# Sheet1.net
KiCad netlist of a schematic drawn in Altium Designer
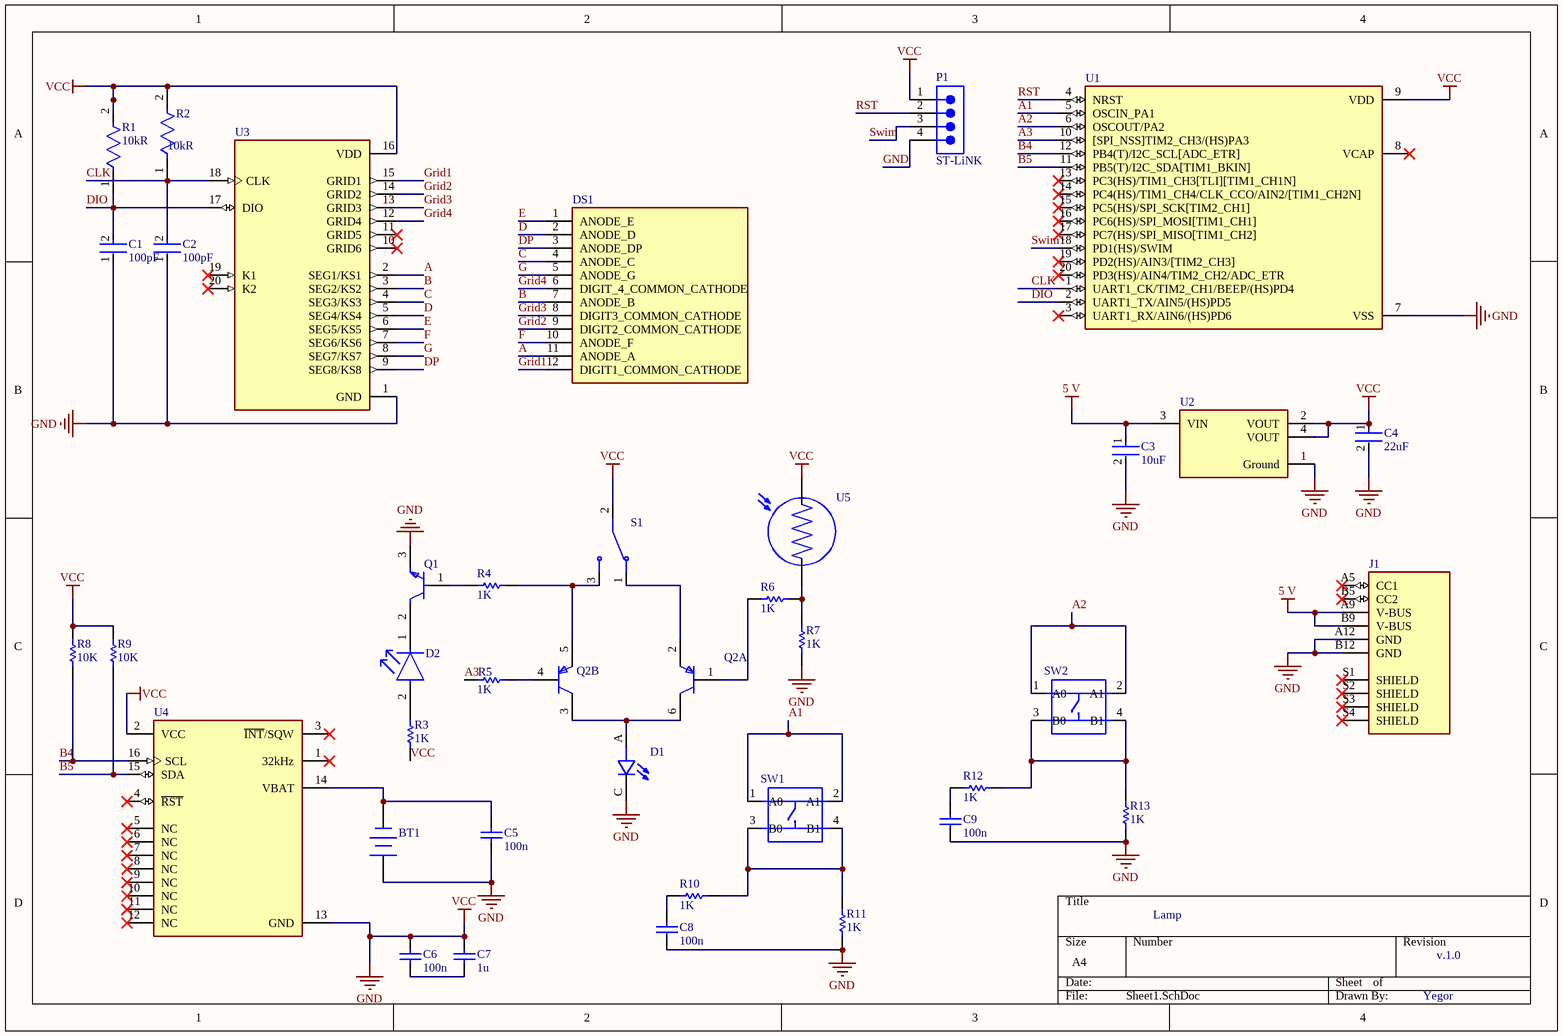
[diagram p0: Sheet1.SchDoc]

(export (version "E")
  (design (tool "Eeschema 10.0.6"))
  (components
    (comp (ref "BT1")
      (value "~")
      (footprint "PANA-CR-2032HFN")
      (description "Coin Cell Battery, 225 mAh, 0.2 mA, 3 V, -30 to 60 degC, Bulk")
      (fields (field (name "MANUFACTURER") "Panasonic"))
      (libsource (lib "Components - 25.08.25 - 13.52") (part "CMP-2000-05296-1"))
    )
    (comp (ref "C1")
      (value "100pF")
      (footprint "FP-C1608-080-0_1-MFG")
      (description "Multilayer Ceramic Capacitors 100pF ±5% 50V C0G SMD 0603")
      (fields (field (name "VOLTAGE") "50V") (field (name "TOLERANCE") "5%"))
      (libsource (lib "Components - 25.08.25 - 11.32") (part "CMP-08246-002637-1"))
    )
    (comp (ref "C2")
      (value "100pF")
      (footprint "FP-C1608-080-0_1-MFG")
      (description "Multilayer Ceramic Capacitors 100pF ±5% 50V C0G SMD 0603")
      (fields (field (name "VOLTAGE") "50V") (field (name "TOLERANCE") "5%"))
      (libsource (lib "Components - 25.08.25 - 11.32") (part "CMP-08246-002637-1"))
    )
    (comp (ref "C3")
      (value "10uF")
      (footprint "FP-CL21-IPC_A")
      (description "CL21 Series 0805 10uF 10V ±20% Tolerance X5R Multilayer Ceramic Chip Capacitor")
      (fields (field (name "TOLERANCE") "20%"))
      (libsource (lib "Components - 25.08.25 - 12.18") (part "CMP-13271-002245-1"))
    )
    (comp (ref "C4")
      (value "22uF")
      (footprint "FP-CL32-IPC_A")
      (description "Cap Ceramic 22uF 6.3V X7R ±20% SMD 1210 +125°C Embossed T/R")
      (fields (field (name "TOLERANCE") "20%"))
      (libsource (lib "Components - 25.08.25 - 12.17") (part "CMP-13271-001877-1"))
    )
    (comp (ref "C5")
      (value "100n")
      (description "Capacitor")
      (libsource (lib "Simulation Generic Components") (part "Capacitor"))
    )
    (comp (ref "C6")
      (value "100n")
      (description "Capacitor")
      (libsource (lib "Simulation Generic Components") (part "Capacitor"))
    )
    (comp (ref "C7")
      (value "1u")
      (description "Capacitor")
      (libsource (lib "Simulation Generic Components") (part "Capacitor"))
    )
    (comp (ref "C8")
      (value "100n")
      (description "Capacitor")
      (libsource (lib "Simulation Generic Components") (part "Capacitor"))
    )
    (comp (ref "C9")
      (value "100n")
      (description "Capacitor")
      (libsource (lib "Simulation Generic Components") (part "Capacitor"))
    )
    (comp (ref "D1")
      (value "~")
      (footprint "LEDC1608X65N")
      (description "CHIP LED WHITE 0603 TOP VIEW")
      (fields (field (name "MP") "LTW-C191TLA"))
      (libsource (lib "LTW-C191TLA") (part "LTW-C191TLA"))
    )
    (comp (ref "D2")
      (value "~")
      (footprint "FP-6_541-5092_01-4-MFG")
      (description "LED RED 0603 SMD")
      (fields
        (field (name "MANUFACTURER") "Vishay")
        (field (name "MANUFACTURER PART NUMBER") "VLMS1300-GS08")
      )
      (libsource (lib "Components - 25.08.25 - 21.29") (part "CMP-02520-000012-1"))
    )
    (comp (ref "DS1")
      (value "~")
      (footprint "AVAGO_HDSP-B09G")
      (fields (field (name "MF") "Broadcom / Avago") (field (name "MP") "HDSP-B09G"))
      (libsource (lib "HDSP-B09G") (part "HDSP-B09G"))
    )
    (comp (ref "J1")
      (value "~")
      (footprint "CUI_UJC-HP-3-SMT-TR")
      (fields (field (name "MP") "UJC-HP-3-SMT-TR"))
      (libsource (lib "UJC-HP-3-SMT-TR") (part "UJC-HP-3-SMT-TR"))
    )
    (comp (ref "P1")
      (value "ST-LiNK")
      (footprint "61300411021")
      (libsource (lib "Components - 25.08.25 - 11.48") (part "CMP-1502-01063-3"))
    )
    (comp (ref "Q1")
      (value "~")
      (footprint "PLZZ0004CA-A_MFG")
      (description "Trans GP BJT NPN 50V 1A 4-Pin(3+Tab) UPAK T/R")
      (libsource (lib "Components - 25.08.25 - 21.28") (part "CMP-00572-18697870-1"))
    )
    (comp (ref "Q2")
      (value "~")
      (footprint "SOT95P280X145-6_P6_064_N")
      (description "Transistor, Bjt, Pair, Pnp, 11V V(Br)Ceo, 14Ma I(C), So")
      (libsource (lib "Components - 25.08.25 - 12.53") (part "CMP-00572-88253858-3"))
    )
    (comp (ref "R1")
      (value "10kR")
      (footprint "FP-CRCW1206-e3-IPC_B")
      (description "RES Thick Film, 10kΩ, 1%, 0.25W, 100ppm/°C, 1206")
      (fields (field (name "TOLERANCE") "1%"))
      (libsource (lib "Components - 25.08.25 - 11.27") (part "CMP-2003-04807-2"))
    )
    (comp (ref "R2")
      (value "10kR")
      (footprint "FP-CRCW1206-e3-IPC_B")
      (description "RES Thick Film, 10kΩ, 1%, 0.25W, 100ppm/°C, 1206")
      (fields (field (name "TOLERANCE") "1%"))
      (libsource (lib "Components - 25.08.25 - 11.27") (part "CMP-2003-04807-2"))
    )
    (comp (ref "R3")
      (value "1K")
      (description "Resistor")
      (libsource (lib "Simulation Generic Components") (part "Resistor"))
    )
    (comp (ref "R4")
      (value "1K")
      (description "Resistor")
      (libsource (lib "Simulation Generic Components") (part "Resistor"))
    )
    (comp (ref "R5")
      (value "1K")
      (description "Resistor")
      (libsource (lib "Simulation Generic Components") (part "Resistor"))
    )
    (comp (ref "R6")
      (value "1K")
      (description "Resistor")
      (libsource (lib "Simulation Generic Components") (part "Resistor"))
    )
    (comp (ref "R7")
      (value "1K")
      (description "Resistor")
      (libsource (lib "Simulation Generic Components") (part "Resistor"))
    )
    (comp (ref "R8")
      (value "10K")
      (description "Resistor")
      (libsource (lib "Simulation Generic Components") (part "Resistor"))
    )
    (comp (ref "R9")
      (value "10K")
      (description "Resistor")
      (libsource (lib "Simulation Generic Components") (part "Resistor"))
    )
    (comp (ref "R10")
      (value "1K")
      (description "Resistor")
      (libsource (lib "Simulation Generic Components") (part "Resistor"))
    )
    (comp (ref "R11")
      (value "1K")
      (description "Resistor")
      (libsource (lib "Simulation Generic Components") (part "Resistor"))
    )
    (comp (ref "R12")
      (value "1K")
      (description "Resistor")
      (libsource (lib "Simulation Generic Components") (part "Resistor"))
    )
    (comp (ref "R13")
      (value "1K")
      (description "Resistor")
      (libsource (lib "Simulation Generic Components") (part "Resistor"))
    )
    (comp (ref "S1")
      (value "~")
      (footprint "SW_MINI-SPDT-SW")
      (fields (field (name "MP") "MINI-SPDT-SW"))
      (libsource (lib "MINI-SPDT-SW") (part "MINI-SPDT-SW"))
    )
    (comp (ref "SW1")
      (value "~")
      (footprint "SW4-SMD-5.2X5.2X1.5MM")
      (description "Switch Tactile N.O. SPST Button Gull Wing 0.05A 12VDC 3.43N SMD T/R")
      (fields (field (name "MF") "ALPS") (field (name "MP") "SKQGAKE010"))
      (libsource (lib "SMD-BUTTON_4P-5.2X5.2X1.5MM-SKQGAKE010_") (part "SMD-BUTTON(4P-5.2X5.2X1.5MM-SKQGAKE010)"))
    )
    (comp (ref "SW2")
      (value "~")
      (footprint "SW4-SMD-5.2X5.2X1.5MM")
      (description "Switch Tactile N.O. SPST Button Gull Wing 0.05A 12VDC 3.43N SMD T/R")
      (fields (field (name "MF") "ALPS") (field (name "MP") "SKQGAKE010"))
      (libsource (lib "SMD-BUTTON_4P-5.2X5.2X1.5MM-SKQGAKE010_") (part "SMD-BUTTON(4P-5.2X5.2X1.5MM-SKQGAKE010)"))
    )
    (comp (ref "U1")
      (value "~")
      (footprint "SOP65P640X120-20N")
      (description "STM8 series Microcontroller IC 8-Bit 16MHz 8KB (8K x 8) FLASH 20-TSSOP")
      (fields (field (name "MF") "STMicroelectronics") (field (name "MP") "STM8S103F3P6"))
      (libsource (lib "STM8S103F3P6") (part "STM8S103F3P6"))
    )
    (comp (ref "U2")
      (value "~")
      (footprint "FP-AMS1117-IPC_A")
      (description "LDO Voltage Regulators 1A, 3.3V")
      (fields
        (field (name "MANUFACTURER PART NUMBER") "AMS1117-3.3")
        (field (name "OCTOPART") "https://octopart.com/ams1117-3.3-advanced+monolithic+systems-25899300")
      )
      (libsource (lib "Components - 25.08.25 - 12.03") (part "CMP-209535-000001-1"))
    )
    (comp (ref "U3")
      (value "~")
      (footprint "DIP778W43P254L2612H431Q20N")
      (description "LED Drive Control Special Circuit")
      (fields (field (name "MF") "Titan Micro Electronics") (field (name "MP") "TM1637"))
      (libsource (lib "TM1637") (part "TM1637"))
    )
    (comp (ref "U4")
      (value "~")
      (footprint "FP-W16-H2-MFG")
      (description "IC RTC CLK/CALENDAR I2C 16-SOIC")
      (libsource (lib "Components - 25.08.25 - 13.49") (part "CMP-0254-00375-2"))
    )
    (comp (ref "U5")
      (value "~")
      (footprint "XDCR_PDV-P8003")
      (description "CdS Cells 520nm 16 ~ 33kOhms @ 10 lux")
      (fields (field (name "MF") "Advanced Photonix") (field (name "MP") "PDV-P8003"))
      (libsource (lib "PDV-P8003") (part "PDV-P8003"))
    )
  )
  (nets
    (net (code "1") (name "/A") (class "Default")
      (node (ref "DS1") (pin "11") (pinfunction "ANODE_A_11") (pintype "passive"))
      (node (ref "U3") (pin "2") (pinfunction "SEG1/KS1_2") (pintype "output"))
    )
    (net (code "2") (name "/A1") (class "Default")
      (node (ref "SW1") (pin "1") (pinfunction "A0_1") (pintype "bidirectional"))
      (node (ref "SW1") (pin "2") (pinfunction "A1_2") (pintype "bidirectional"))
      (node (ref "U1") (pin "5") (pinfunction "OSCIN_PA1_5") (pintype "bidirectional"))
    )
    (net (code "3") (name "/A2") (class "Default")
      (node (ref "SW2") (pin "1") (pinfunction "A0_1") (pintype "bidirectional"))
      (node (ref "SW2") (pin "2") (pinfunction "A1_2") (pintype "bidirectional"))
      (node (ref "U1") (pin "6") (pinfunction "OSCOUT/PA2_6") (pintype "bidirectional"))
    )
    (net (code "4") (name "/A3") (class "Default")
      (node (ref "R5") (pin "2") (pinfunction "2_2") (pintype "passive"))
      (node (ref "U1") (pin "10") (pinfunction "[SPI_NSS]TIM2_CH3/(HS)PA3_10") (pintype "bidirectional"))
    )
    (net (code "5") (name "/B") (class "Default")
      (node (ref "DS1") (pin "7") (pinfunction "ANODE_B_7") (pintype "passive"))
      (node (ref "U3") (pin "3") (pinfunction "SEG2/KS2_3") (pintype "output"))
    )
    (net (code "6") (name "/B4") (class "Default")
      (node (ref "R8") (pin "1") (pinfunction "1_1") (pintype "passive"))
      (node (ref "U1") (pin "12") (pinfunction "PB4(T)/I2C_SCL[ADC_ETR]_12") (pintype "bidirectional"))
      (node (ref "U4") (pin "16") (pinfunction "SCL_16") (pintype "input"))
    )
    (net (code "7") (name "/B5") (class "Default")
      (node (ref "R9") (pin "1") (pinfunction "1_1") (pintype "passive"))
      (node (ref "U1") (pin "11") (pinfunction "PB5(T)/I2C_SDA[TIM1_BKIN]_11") (pintype "bidirectional"))
      (node (ref "U4") (pin "15") (pinfunction "SDA_15") (pintype "bidirectional"))
    )
    (net (code "8") (name "/C") (class "Default")
      (node (ref "DS1") (pin "4") (pinfunction "ANODE_C_4") (pintype "passive"))
      (node (ref "U3") (pin "4") (pinfunction "SEG3/KS3_4") (pintype "output"))
    )
    (net (code "9") (name "/CLK") (class "Default")
      (node (ref "C2") (pin "2") (pinfunction "2_2") (pintype "passive"))
      (node (ref "R2") (pin "1") (pinfunction "1_1") (pintype "passive"))
      (node (ref "U1") (pin "1") (pinfunction "UART1_CK/TIM2_CH1/BEEP/(HS)PD4_1") (pintype "bidirectional"))
      (node (ref "U3") (pin "18") (pinfunction "CLK_18") (pintype "input"))
    )
    (net (code "10") (name "/D") (class "Default")
      (node (ref "DS1") (pin "2") (pinfunction "ANODE_D_2") (pintype "passive"))
      (node (ref "U3") (pin "5") (pinfunction "SEG4/KS4_5") (pintype "output"))
    )
    (net (code "11") (name "/DIO") (class "Default")
      (node (ref "C1") (pin "2") (pinfunction "2_2") (pintype "passive"))
      (node (ref "R1") (pin "1") (pinfunction "1_1") (pintype "passive"))
      (node (ref "U1") (pin "2") (pinfunction "UART1_TX/AIN5/(HS)PD5_2") (pintype "bidirectional"))
      (node (ref "U3") (pin "17") (pinfunction "DIO_17") (pintype "bidirectional"))
    )
    (net (code "12") (name "/DP") (class "Default")
      (node (ref "DS1") (pin "3") (pinfunction "ANODE_DP_3") (pintype "passive"))
      (node (ref "U3") (pin "9") (pinfunction "SEG8/KS8_9") (pintype "output"))
    )
    (net (code "13") (name "/E") (class "Default")
      (node (ref "DS1") (pin "1") (pinfunction "ANODE_E_1") (pintype "passive"))
      (node (ref "U3") (pin "6") (pinfunction "SEG5/KS5_6") (pintype "output"))
    )
    (net (code "14") (name "/F") (class "Default")
      (node (ref "DS1") (pin "10") (pinfunction "ANODE_F_10") (pintype "passive"))
      (node (ref "U3") (pin "7") (pinfunction "SEG6/KS6_7") (pintype "output"))
    )
    (net (code "15") (name "/G") (class "Default")
      (node (ref "DS1") (pin "5") (pinfunction "ANODE_G_5") (pintype "passive"))
      (node (ref "U3") (pin "8") (pinfunction "SEG7/KS7_8") (pintype "output"))
    )
    (net (code "16") (name "/Grid1") (class "Default")
      (node (ref "DS1") (pin "12") (pinfunction "DIGIT1_COMMON_CATHODE_12") (pintype "passive"))
      (node (ref "U3") (pin "15") (pinfunction "GRID1_15") (pintype "output"))
    )
    (net (code "17") (name "/Grid2") (class "Default")
      (node (ref "DS1") (pin "9") (pinfunction "DIGIT2_COMMON_CATHODE_9") (pintype "passive"))
      (node (ref "U3") (pin "14") (pinfunction "GRID2_14") (pintype "output"))
    )
    (net (code "18") (name "/Grid3") (class "Default")
      (node (ref "DS1") (pin "8") (pinfunction "DIGIT3_COMMON_CATHODE_8") (pintype "passive"))
      (node (ref "U3") (pin "13") (pinfunction "GRID3_13") (pintype "output"))
    )
    (net (code "19") (name "/Grid4") (class "Default")
      (node (ref "DS1") (pin "6") (pinfunction "DIGIT_4_COMMON_CATHODE_6") (pintype "passive"))
      (node (ref "U3") (pin "12") (pinfunction "GRID4_12") (pintype "output"))
    )
    (net (code "20") (name "/RST") (class "Default")
      (node (ref "P1") (pin "2") (pinfunction "2_2") (pintype "passive"))
      (node (ref "U1") (pin "4") (pinfunction "NRST_4") (pintype "bidirectional"))
    )
    (net (code "21") (name "/Swim") (class "Default")
      (node (ref "P1") (pin "3") (pinfunction "3_3") (pintype "passive"))
      (node (ref "U1") (pin "18") (pinfunction "PD1(HS)/SWIM_18") (pintype "bidirectional"))
    )
    (net (code "22") (name "5 V") (class "Default")
      (node (ref "C3") (pin "1") (pinfunction "1_1") (pintype "passive"))
      (node (ref "J1") (pin "A9") (pinfunction "V-BUS_A9") (pintype "power_in"))
      (node (ref "J1") (pin "B9") (pinfunction "V-BUS_B9") (pintype "power_in"))
      (node (ref "U2") (pin "3") (pinfunction "VIN_3") (pintype "power_in"))
    )
    (net (code "23") (name "GND") (class "Default")
      (node (ref "BT1") (pin "1") (pinfunction "+_1") (pintype "passive"))
      (node (ref "C1") (pin "1") (pinfunction "1_1") (pintype "passive"))
      (node (ref "C2") (pin "1") (pinfunction "1_1") (pintype "passive"))
      (node (ref "C3") (pin "2") (pinfunction "2_2") (pintype "passive"))
      (node (ref "C4") (pin "1") (pinfunction "1_1") (pintype "passive"))
      (node (ref "C4") (pin "2") (pinfunction "2_2") (pintype "passive"))
      (node (ref "C5") (pin "1") (pinfunction "1_1") (pintype "passive"))
      (node (ref "C6") (pin "2") (pinfunction "2_2") (pintype "passive"))
      (node (ref "C7") (pin "2") (pinfunction "2_2") (pintype "passive"))
      (node (ref "C8") (pin "1") (pinfunction "1_1") (pintype "passive"))
      (node (ref "C9") (pin "1") (pinfunction "1_1") (pintype "passive"))
      (node (ref "D1") (pin "C") (pinfunction "C_C") (pintype "passive"))
      (node (ref "J1") (pin "A12") (pinfunction "GND_A12") (pintype "power_in"))
      (node (ref "J1") (pin "B12") (pinfunction "GND_B12") (pintype "power_in"))
      (node (ref "P1") (pin "1") (pinfunction "1_1") (pintype "passive"))
      (node (ref "P1") (pin "4") (pinfunction "4_4") (pintype "passive"))
      (node (ref "Q1") (pin "3") (pinfunction "EMITTER_3") (pintype "passive"))
      (node (ref "R1") (pin "2") (pinfunction "2_2") (pintype "passive"))
      (node (ref "R11") (pin "1") (pinfunction "1_1") (pintype "passive"))
      (node (ref "R13") (pin "1") (pinfunction "1_1") (pintype "passive"))
      (node (ref "R2") (pin "2") (pinfunction "2_2") (pintype "passive"))
      (node (ref "R3") (pin "1") (pinfunction "1_1") (pintype "passive"))
      (node (ref "R7") (pin "1") (pinfunction "1_1") (pintype "passive"))
      (node (ref "R8") (pin "2") (pinfunction "2_2") (pintype "passive"))
      (node (ref "R9") (pin "2") (pinfunction "2_2") (pintype "passive"))
      (node (ref "S1") (pin "2") (pinfunction "2_2") (pintype "passive"))
      (node (ref "U1") (pin "7") (pinfunction "VSS_7") (pintype "power_in"))
      (node (ref "U1") (pin "9") (pinfunction "VDD_9") (pintype "power_in"))
      (node (ref "U2") (pin "1") (pinfunction "Ground_1") (pintype "power_in"))
      (node (ref "U2") (pin "2") (pinfunction "VOUT_2") (pintype "passive"))
      (node (ref "U2") (pin "4") (pinfunction "VOUT_4") (pintype "passive"))
      (node (ref "U3") (pin "1") (pinfunction "GND_1") (pintype "power_in"))
      (node (ref "U3") (pin "16") (pinfunction "VDD_16") (pintype "power_in"))
      (node (ref "U4") (pin "13") (pinfunction "GND_13") (pintype "power_in"))
      (node (ref "U4") (pin "2") (pinfunction "VCC_2") (pintype "power_in"))
      (node (ref "U5") (pin "2") (pinfunction "2_2") (pintype "passive"))
    )
    (net (code "24") (name "Net-(BT1--)") (class "Default")
      (node (ref "BT1") (pin "2") (pinfunction "-_2") (pintype "passive"))
      (node (ref "C5") (pin "2") (pinfunction "2_2") (pintype "passive"))
      (node (ref "U4") (pin "14") (pinfunction "VBAT_14") (pintype "power_in"))
    )
    (net (code "25") (name "Net-(C6-Pad1)") (class "Default")
      (node (ref "C6") (pin "1") (pinfunction "1_1") (pintype "passive"))
      (node (ref "C7") (pin "1") (pinfunction "1_1") (pintype "passive"))
    )
    (net (code "26") (name "Net-(C8-Pad2)") (class "Default")
      (node (ref "C8") (pin "2") (pinfunction "2_2") (pintype "passive"))
      (node (ref "R10") (pin "1") (pinfunction "1_1") (pintype "passive"))
    )
    (net (code "27") (name "Net-(C9-Pad2)") (class "Default")
      (node (ref "C9") (pin "2") (pinfunction "2_2") (pintype "passive"))
      (node (ref "R12") (pin "1") (pinfunction "1_1") (pintype "passive"))
    )
    (net (code "28") (name "Net-(D2-A)") (class "Default")
      (node (ref "D2") (pin "2") (pinfunction "A_2") (pintype "passive"))
      (node (ref "R3") (pin "2") (pinfunction "2_2") (pintype "passive"))
    )
    (net (code "29") (name "Net-(D2-C)") (class "Default")
      (node (ref "D2") (pin "1") (pinfunction "C_1") (pintype "passive"))
      (node (ref "Q1") (pin "2") (pinfunction "COLLECTOR_2") (pintype "passive"))
    )
    (net (code "30") (name "Net-(Q1-BASE)") (class "Default")
      (node (ref "Q1") (pin "1") (pinfunction "BASE_1") (pintype "passive"))
      (node (ref "R4") (pin "1") (pinfunction "1_1") (pintype "passive"))
    )
    (net (code "31") (name "Net-(Q2A-1_BASE)") (class "Default")
      (node (ref "Q2") (pin "1") (pinfunction "1_BASE_1") (pintype "passive"))
      (node (ref "R6") (pin "1") (pinfunction "1_1") (pintype "passive"))
    )
    (net (code "32") (name "Net-(Q2A-1_COLLECTOR)") (class "Default")
      (node (ref "D1") (pin "A") (pinfunction "A_A") (pintype "passive"))
      (node (ref "Q2") (pin "3") (pinfunction "2_COLLECTOR_3") (pintype "passive"))
      (node (ref "Q2") (pin "6") (pinfunction "1_COLLECTOR_6") (pintype "passive"))
    )
    (net (code "33") (name "Net-(Q2A-1_EMITTER)") (class "Default")
      (node (ref "Q2") (pin "2") (pinfunction "1_EMITTER_2") (pintype "passive"))
      (node (ref "S1") (pin "1") (pinfunction "1_1") (pintype "passive"))
    )
    (net (code "34") (name "Net-(Q2B-2_BASE)") (class "Default")
      (node (ref "Q2") (pin "4") (pinfunction "2_BASE_4") (pintype "passive"))
      (node (ref "R5") (pin "1") (pinfunction "1_1") (pintype "passive"))
    )
    (net (code "35") (name "Net-(Q2B-2_EMITTER)") (class "Default")
      (node (ref "Q2") (pin "5") (pinfunction "2_EMITTER_5") (pintype "passive"))
      (node (ref "R4") (pin "2") (pinfunction "2_2") (pintype "passive"))
      (node (ref "S1") (pin "3") (pinfunction "3_3") (pintype "passive"))
    )
    (net (code "36") (name "Net-(R6-Pad2)") (class "Default")
      (node (ref "R6") (pin "2") (pinfunction "2_2") (pintype "passive"))
      (node (ref "R7") (pin "2") (pinfunction "2_2") (pintype "passive"))
      (node (ref "U5") (pin "1") (pinfunction "1_1") (pintype "passive"))
    )
    (net (code "37") (name "Net-(SW1-B0)") (class "Default")
      (node (ref "R10") (pin "2") (pinfunction "2_2") (pintype "passive"))
      (node (ref "R11") (pin "2") (pinfunction "2_2") (pintype "passive"))
      (node (ref "SW1") (pin "3") (pinfunction "B0_3") (pintype "bidirectional"))
      (node (ref "SW1") (pin "4") (pinfunction "B1_4") (pintype "bidirectional"))
    )
    (net (code "38") (name "Net-(SW2-B0)") (class "Default")
      (node (ref "R12") (pin "2") (pinfunction "2_2") (pintype "passive"))
      (node (ref "R13") (pin "2") (pinfunction "2_2") (pintype "passive"))
      (node (ref "SW2") (pin "3") (pinfunction "B0_3") (pintype "bidirectional"))
      (node (ref "SW2") (pin "4") (pinfunction "B1_4") (pintype "bidirectional"))
    )
    (net (code "39") (name "unconnected-(J1-CC1-PadA5)") (class "Default")
      (node (ref "J1") (pin "A5") (pinfunction "CC1_A5") (pintype "bidirectional+no_connect"))
    )
    (net (code "40") (name "unconnected-(J1-CC2-PadB5)") (class "Default")
      (node (ref "J1") (pin "B5") (pinfunction "CC2_B5") (pintype "bidirectional+no_connect"))
    )
    (net (code "41") (name "unconnected-(J1-SHIELD-PadS1)") (class "Default")
      (node (ref "J1") (pin "S1") (pinfunction "SHIELD_S1") (pintype "passive+no_connect"))
    )
    (net (code "42") (name "unconnected-(J1-SHIELD-PadS2)") (class "Default")
      (node (ref "J1") (pin "S2") (pinfunction "SHIELD_S2") (pintype "passive+no_connect"))
    )
    (net (code "43") (name "unconnected-(J1-SHIELD-PadS3)") (class "Default")
      (node (ref "J1") (pin "S3") (pinfunction "SHIELD_S3") (pintype "passive+no_connect"))
    )
    (net (code "44") (name "unconnected-(J1-SHIELD-PadS4)") (class "Default")
      (node (ref "J1") (pin "S4") (pinfunction "SHIELD_S4") (pintype "passive+no_connect"))
    )
    (net (code "45") (name "unconnected-(U1-PC3(HS){slash}TIM1_CH3[TLI][TIM1_CH1N]-Pad13)") (class "Default")
      (node (ref "U1") (pin "13") (pinfunction "PC3(HS)/TIM1_CH3[TLI][TIM1_CH1N]_13") (pintype "bidirectional+no_connect"))
    )
    (net (code "46") (name "unconnected-(U1-PC4(HS){slash}TIM1_CH4{slash}CLK_CCO{slash}AIN2{slash}[TIM1_CH2N]-Pad14)") (class "Default")
      (node (ref "U1") (pin "14") (pinfunction "PC4(HS)/TIM1_CH4/CLK_CCO/AIN2/[TIM1_CH2N]_14") (pintype "bidirectional+no_connect"))
    )
    (net (code "47") (name "unconnected-(U1-PC5(HS){slash}SPI_SCK[TIM2_CH1]-Pad15)") (class "Default")
      (node (ref "U1") (pin "15") (pinfunction "PC5(HS)/SPI_SCK[TIM2_CH1]_15") (pintype "bidirectional+no_connect"))
    )
    (net (code "48") (name "unconnected-(U1-PC6(HS){slash}SPI_MOSI[TIM1_CH1]-Pad16)") (class "Default")
      (node (ref "U1") (pin "16") (pinfunction "PC6(HS)/SPI_MOSI[TIM1_CH1]_16") (pintype "bidirectional+no_connect"))
    )
    (net (code "49") (name "unconnected-(U1-PC7(HS){slash}SPI_MISO[TIM1_CH2]-Pad17)") (class "Default")
      (node (ref "U1") (pin "17") (pinfunction "PC7(HS)/SPI_MISO[TIM1_CH2]_17") (pintype "bidirectional+no_connect"))
    )
    (net (code "50") (name "unconnected-(U1-PD2(HS){slash}AIN3{slash}[TIM2_CH3]-Pad19)") (class "Default")
      (node (ref "U1") (pin "19") (pinfunction "PD2(HS)/AIN3/[TIM2_CH3]_19") (pintype "bidirectional+no_connect"))
    )
    (net (code "51") (name "unconnected-(U1-PD3(HS){slash}AIN4{slash}TIM2_CH2{slash}ADC_ETR-Pad20)") (class "Default")
      (node (ref "U1") (pin "20") (pinfunction "PD3(HS)/AIN4/TIM2_CH2/ADC_ETR_20") (pintype "bidirectional+no_connect"))
    )
    (net (code "52") (name "unconnected-(U1-UART1_RX{slash}AIN6{slash}(HS)PD6-Pad3)") (class "Default")
      (node (ref "U1") (pin "3") (pinfunction "UART1_RX/AIN6/(HS)PD6_3") (pintype "bidirectional+no_connect"))
    )
    (net (code "53") (name "unconnected-(U1-VCAP-Pad8)") (class "Default")
      (node (ref "U1") (pin "8") (pinfunction "VCAP_8") (pintype "passive+no_connect"))
    )
    (net (code "54") (name "unconnected-(U3-GRID5-Pad11)") (class "Default")
      (node (ref "U3") (pin "11") (pinfunction "GRID5_11") (pintype "output+no_connect"))
    )
    (net (code "55") (name "unconnected-(U3-GRID6-Pad10)") (class "Default")
      (node (ref "U3") (pin "10") (pinfunction "GRID6_10") (pintype "output+no_connect"))
    )
    (net (code "56") (name "unconnected-(U3-K1-Pad19)") (class "Default")
      (node (ref "U3") (pin "19") (pinfunction "K1_19") (pintype "input+no_connect"))
    )
    (net (code "57") (name "unconnected-(U3-K2-Pad20)") (class "Default")
      (node (ref "U3") (pin "20") (pinfunction "K2_20") (pintype "input+no_connect"))
    )
    (net (code "58") (name "unconnected-(U4-32kHz-Pad1)") (class "Default")
      (node (ref "U4") (pin "1") (pinfunction "32kHz_1") (pintype "open_collector+no_connect"))
    )
    (net (code "59") (name "unconnected-(U4-NC-Pad5)") (class "Default")
      (node (ref "U4") (pin "5") (pinfunction "NC_5") (pintype "passive+no_connect"))
    )
    (net (code "60") (name "unconnected-(U4-NC-Pad6)") (class "Default")
      (node (ref "U4") (pin "6") (pinfunction "NC_6") (pintype "passive+no_connect"))
    )
    (net (code "61") (name "unconnected-(U4-NC-Pad7)") (class "Default")
      (node (ref "U4") (pin "7") (pinfunction "NC_7") (pintype "passive+no_connect"))
    )
    (net (code "62") (name "unconnected-(U4-NC-Pad8)") (class "Default")
      (node (ref "U4") (pin "8") (pinfunction "NC_8") (pintype "passive+no_connect"))
    )
    (net (code "63") (name "unconnected-(U4-NC-Pad9)") (class "Default")
      (node (ref "U4") (pin "9") (pinfunction "NC_9") (pintype "passive+no_connect"))
    )
    (net (code "64") (name "unconnected-(U4-NC-Pad10)") (class "Default")
      (node (ref "U4") (pin "10") (pinfunction "NC_10") (pintype "passive+no_connect"))
    )
    (net (code "65") (name "unconnected-(U4-NC-Pad11)") (class "Default")
      (node (ref "U4") (pin "11") (pinfunction "NC_11") (pintype "passive+no_connect"))
    )
    (net (code "66") (name "unconnected-(U4-NC-Pad12)") (class "Default")
      (node (ref "U4") (pin "12") (pinfunction "NC_12") (pintype "passive+no_connect"))
    )
    (net (code "67") (name "unconnected-(U4-~{INT}{slash}SQW-Pad3)") (class "Default")
      (node (ref "U4") (pin "3") (pinfunction "~{INT}/SQW_3") (pintype "open_collector+no_connect"))
    )
    (net (code "68") (name "unconnected-(U4-~{RST}-Pad4)") (class "Default")
      (node (ref "U4") (pin "4") (pinfunction "~{RST}_4") (pintype "bidirectional+no_connect"))
    )
  )
)
